# HydraNFC_v1_1_Rev1.net
KiCad netlist of a schematic drawn in EAGLE
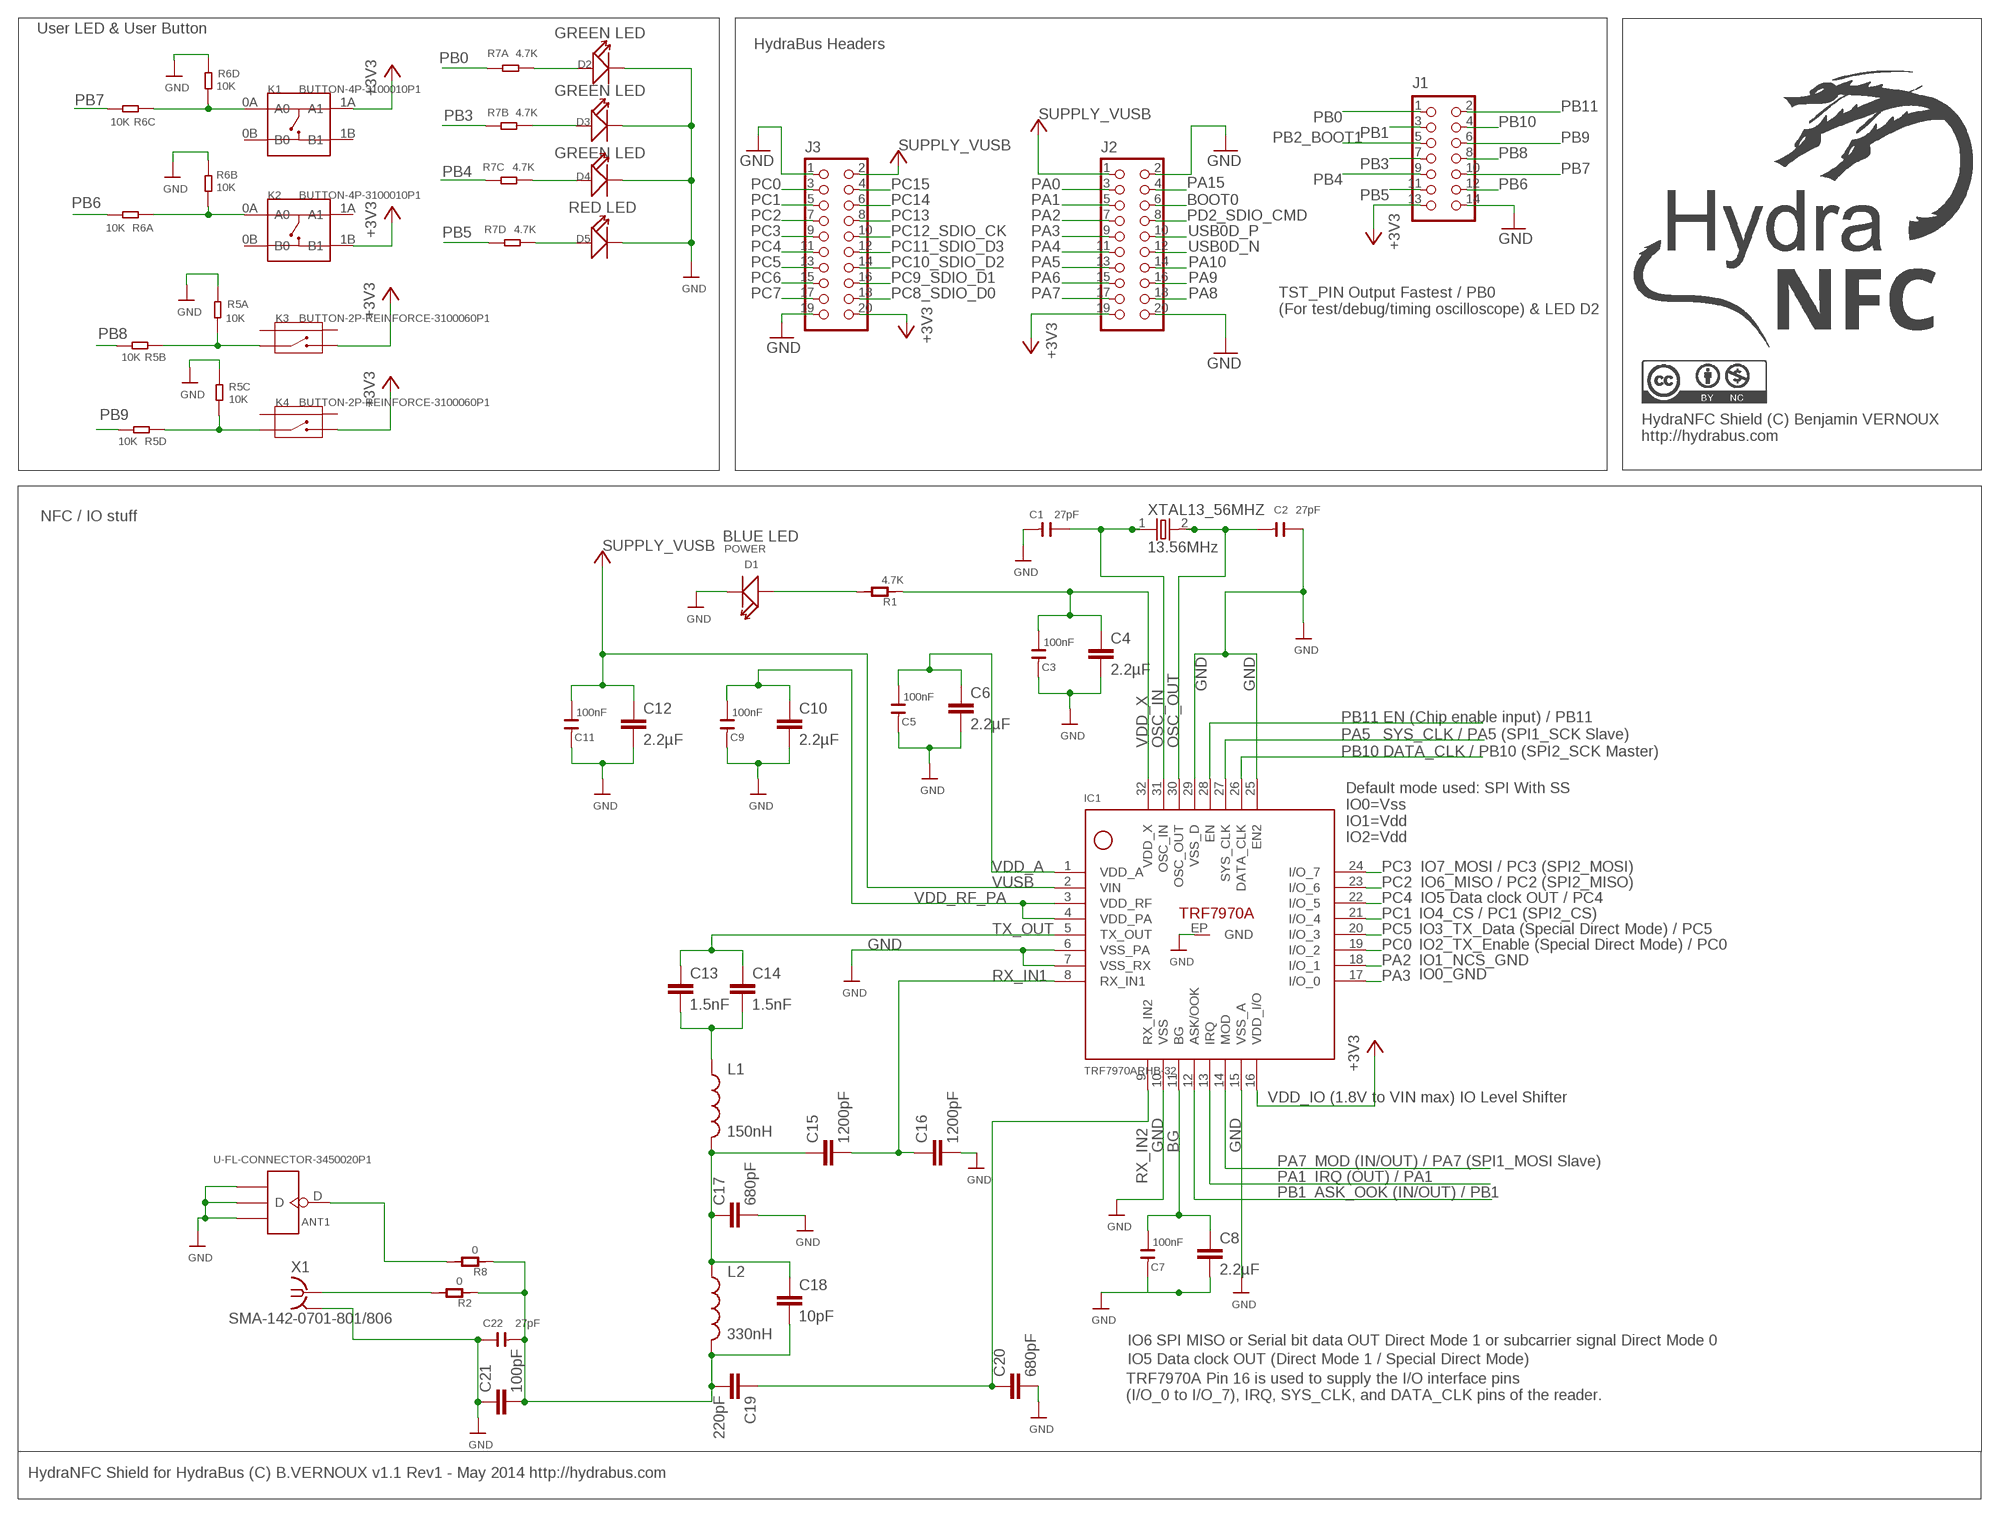
[diagram p0: schematic, sheet 1]

(export (version "E")
  (design (tool "Eeschema 10.0.6"))
  (components
    (comp (ref "ANT1")
      (value "U-FL-CONNECTOR-3450020P1")
      (footprint "eagle-import:U-FL")
      (libsource (lib "eagle-import") (part "U-FL-CONNECTOR-3450020P1"))
    )
    (comp (ref "C1")
      (value "27pF")
      (footprint "eagle-import:C0603")
      (libsource (lib "eagle-import") (part "C-0603"))
    )
    (comp (ref "C2")
      (value "27pF")
      (footprint "eagle-import:C0603")
      (libsource (lib "eagle-import") (part "C-0603"))
    )
    (comp (ref "C3")
      (value "100nF")
      (footprint "eagle-import:C0603")
      (libsource (lib "eagle-import") (part "C-0603"))
    )
    (comp (ref "C4")
      (value "2.2µF")
      (footprint "eagle-import:C805")
      (libsource (lib "eagle-import") (part "CAPC805"))
    )
    (comp (ref "C5")
      (value "100nF")
      (footprint "eagle-import:C0603")
      (libsource (lib "eagle-import") (part "C-0603"))
    )
    (comp (ref "C6")
      (value "2.2µF")
      (footprint "eagle-import:C805")
      (libsource (lib "eagle-import") (part "CAPC805"))
    )
    (comp (ref "C7")
      (value "100nF")
      (footprint "eagle-import:C0603")
      (libsource (lib "eagle-import") (part "C-0603"))
    )
    (comp (ref "C8")
      (value "2.2µF")
      (footprint "eagle-import:C805")
      (libsource (lib "eagle-import") (part "CAPC805"))
    )
    (comp (ref "C9")
      (value "100nF")
      (footprint "eagle-import:C0603")
      (libsource (lib "eagle-import") (part "C-0603"))
    )
    (comp (ref "C10")
      (value "2.2µF")
      (footprint "eagle-import:C805")
      (libsource (lib "eagle-import") (part "CAPC805"))
    )
    (comp (ref "C11")
      (value "100nF")
      (footprint "eagle-import:C0603")
      (libsource (lib "eagle-import") (part "C-0603"))
    )
    (comp (ref "C12")
      (value "2.2µF")
      (footprint "eagle-import:C805")
      (libsource (lib "eagle-import") (part "CAPC805"))
    )
    (comp (ref "C13")
      (value "1.5nF")
      (footprint "eagle-import:C805")
      (libsource (lib "eagle-import") (part "CAPC805"))
    )
    (comp (ref "C14")
      (value "1.5nF")
      (footprint "eagle-import:C805")
      (libsource (lib "eagle-import") (part "CAPC805"))
    )
    (comp (ref "C15")
      (value "1200pF")
      (footprint "eagle-import:C805")
      (libsource (lib "eagle-import") (part "CAPC805"))
    )
    (comp (ref "C16")
      (value "1200pF")
      (footprint "eagle-import:C805")
      (libsource (lib "eagle-import") (part "CAPC805"))
    )
    (comp (ref "C17")
      (value "680pF")
      (footprint "eagle-import:C805")
      (libsource (lib "eagle-import") (part "CAPC805"))
    )
    (comp (ref "C18")
      (value "10pF")
      (footprint "eagle-import:C805")
      (libsource (lib "eagle-import") (part "CAPC805"))
    )
    (comp (ref "C19")
      (value "220pF")
      (footprint "eagle-import:C805")
      (libsource (lib "eagle-import") (part "CAPC805"))
    )
    (comp (ref "C20")
      (value "680pF")
      (footprint "eagle-import:C805")
      (libsource (lib "eagle-import") (part "CAPC805"))
    )
    (comp (ref "C21")
      (value "100pF")
      (footprint "eagle-import:C805")
      (libsource (lib "eagle-import") (part "CAPC805"))
    )
    (comp (ref "C22")
      (value "27pF")
      (footprint "eagle-import:C0603")
      (libsource (lib "eagle-import") (part "C-0603"))
    )
    (comp (ref "D1")
      (value "POWER")
      (footprint "eagle-import:LED0603")
      (libsource (lib "eagle-import") (part "LED"))
    )
    (comp (ref "D2")
      (value "LED")
      (footprint "eagle-import:LED0603")
      (libsource (lib "eagle-import") (part "OPL Eagle Library_LED"))
    )
    (comp (ref "D3")
      (value "LED")
      (footprint "eagle-import:LED0603")
      (libsource (lib "eagle-import") (part "OPL Eagle Library_LED"))
    )
    (comp (ref "D4")
      (value "LED")
      (footprint "eagle-import:LED0603")
      (libsource (lib "eagle-import") (part "OPL Eagle Library_LED"))
    )
    (comp (ref "D5")
      (value "LED")
      (footprint "eagle-import:LED0603")
      (libsource (lib "eagle-import") (part "OPL Eagle Library_LED"))
    )
    (comp (ref "IC1")
      (value "TRF7970ARHB-32")
      (footprint "eagle-import:TRF7970A")
      (libsource (lib "eagle-import") (part "TRF7970A"))
    )
    (comp (ref "J1")
      (value "HYDRABUS_SHIELD_CON_HEADER_2X07")
      (footprint "eagle-import:HYDRABUS_SHIELD_M2X7")
      (libsource (lib "eagle-import") (part "HYDRABUS_SHIELD_CON_HEADER_2X07"))
    )
    (comp (ref "J2")
      (value "HYDRABUS_SHIELD_CON_HEADER_2X10")
      (footprint "eagle-import:HYDRABUS_SHIELD_M2X10")
      (libsource (lib "eagle-import") (part "HYDRABUS_SHIELD_CON_HEADER_2X10"))
    )
    (comp (ref "J3")
      (value "HYDRABUS_SHIELD_CON_HEADER_2X10")
      (footprint "eagle-import:HYDRABUS_SHIELD_M2X10")
      (libsource (lib "eagle-import") (part "HYDRABUS_SHIELD_CON_HEADER_2X10"))
    )
    (comp (ref "K1")
      (value "BUTTON-4P-3100010P1")
      (footprint "eagle-import:4P-SMD-6.0X6.0X5.0H")
      (libsource (lib "eagle-import") (part "BUTTON-4P-3100010P1"))
    )
    (comp (ref "K2")
      (value "BUTTON-4P-3100010P1")
      (footprint "eagle-import:4P-SMD-6.0X6.0X5.0H")
      (libsource (lib "eagle-import") (part "BUTTON-4P-3100010P1"))
    )
    (comp (ref "K3")
      (value "BUTTON-2P-REINFORCE-3100060P1")
      (footprint "eagle-import:4P-SMD-7.0X3.5X3.5H-90D")
      (libsource (lib "eagle-import") (part "BUTTON-2P-REINFORCE-3100060P1"))
    )
    (comp (ref "K4")
      (value "BUTTON-2P-REINFORCE-3100060P1")
      (footprint "eagle-import:4P-SMD-7.0X3.5X3.5H-90D")
      (libsource (lib "eagle-import") (part "BUTTON-2P-REINFORCE-3100060P1"))
    )
    (comp (ref "L1")
      (value "150nH")
      (footprint "eagle-import:1210")
      (libsource (lib "eagle-import") (part "INDUCTOR1210"))
    )
    (comp (ref "L2")
      (value "330nH")
      (footprint "eagle-import:1210")
      (libsource (lib "eagle-import") (part "INDUCTOR1210"))
    )
    (comp (ref "R1")
      (value "4.7K")
      (footprint "eagle-import:R0603")
      (libsource (lib "eagle-import") (part "R-0603"))
    )
    (comp (ref "R2")
      (value "0")
      (footprint "eagle-import:R0603")
      (libsource (lib "eagle-import") (part "R-0603"))
    )
    (comp (ref "R5")
      (value "10K")
      (footprint "eagle-import:R1206-8")
      (fields (field (name "OPL") "0040070P1"))
      (libsource (lib "eagle-import") (part "R-4R"))
    )
    (comp (ref "R6")
      (value "10K")
      (footprint "eagle-import:R1206-8")
      (fields (field (name "OPL") "0040070P1"))
      (libsource (lib "eagle-import") (part "R-4R"))
    )
    (comp (ref "R7")
      (value "4.7K")
      (footprint "eagle-import:R1206-8")
      (fields (field (name "OPL") "0040040P1"))
      (libsource (lib "eagle-import") (part "R-4R"))
    )
    (comp (ref "R8")
      (value "0")
      (footprint "eagle-import:R0603")
      (libsource (lib "eagle-import") (part "R-0603"))
    )
    (comp (ref "X1")
      (value "SMA-142-0701-801/806")
      (footprint "eagle-import:J502-ND-142-0701-801_806")
      (fields (field (name "MF") "JOHNSON COMPONENTS") (field (name "MPN") "142-0701-801"))
      (libsource (lib "eagle-import") (part "SMA-142-0701-801/806"))
    )
    (comp (ref "XTAL13_56MHZ")
      (value "13.56MHz")
      (footprint "eagle-import:HC-49U")
      (libsource (lib "eagle-import") (part "OSC-XTAL"))
    )
  )
  (nets
    (net (code "1") (name "+3V3") (class "Default")
      (node (ref "IC1") (pin "16") (pinfunction "VDD_I/O_16") (pintype "input"))
      (node (ref "J1") (pin "13") (pinfunction "13_13") (pintype "passive"))
      (node (ref "J2") (pin "19") (pinfunction "19_19") (pintype "passive"))
      (node (ref "J3") (pin "20") (pinfunction "20_20") (pintype "passive"))
      (node (ref "K1") (pin "1A") (pinfunction "A1_1A") (pintype "bidirectional"))
      (node (ref "K2") (pin "1B") (pinfunction "B1_1B") (pintype "bidirectional"))
      (node (ref "K3") (pin "2") (pinfunction "2_2") (pintype "bidirectional"))
      (node (ref "K4") (pin "2") (pinfunction "2_2") (pintype "bidirectional"))
    )
    (net (code "2") (name "/BG") (class "Default")
      (node (ref "C7") (pin "2") (pinfunction "2_2") (pintype "bidirectional"))
      (node (ref "C8") (pin "1") (pinfunction "1_1") (pintype "passive"))
      (node (ref "IC1") (pin "11") (pinfunction "BG_11") (pintype "output"))
    )
    (net (code "3") (name "/BOOT0") (class "Default")
      (node (ref "J2") (pin "6") (pinfunction "6_6") (pintype "passive"))
    )
    (net (code "4") (name "/OSC_IN") (class "Default")
      (node (ref "C1") (pin "2") (pinfunction "2_2") (pintype "bidirectional"))
      (node (ref "IC1") (pin "31") (pinfunction "OSC_IN_31") (pintype "bidirectional"))
      (node (ref "XTAL13_56MHZ") (pin "1") (pinfunction "1_1") (pintype "passive"))
    )
    (net (code "5") (name "/OSC_OUT") (class "Default")
      (node (ref "C2") (pin "1") (pinfunction "1_1") (pintype "bidirectional"))
      (node (ref "IC1") (pin "30") (pinfunction "OSC_OUT_30") (pintype "output"))
      (node (ref "XTAL13_56MHZ") (pin "2") (pinfunction "2_2") (pintype "passive"))
    )
    (net (code "6") (name "/PA0") (class "Default")
      (node (ref "J2") (pin "3") (pinfunction "3_3") (pintype "passive"))
    )
    (net (code "7") (name "/PA1") (class "Default")
      (node (ref "IC1") (pin "13") (pinfunction "IRQ_13") (pintype "output"))
      (node (ref "J2") (pin "5") (pinfunction "5_5") (pintype "passive"))
    )
    (net (code "8") (name "/PA2") (class "Default")
      (node (ref "IC1") (pin "18") (pinfunction "I/O_1_18") (pintype "bidirectional"))
      (node (ref "J2") (pin "7") (pinfunction "7_7") (pintype "passive"))
    )
    (net (code "9") (name "/PA3") (class "Default")
      (node (ref "IC1") (pin "17") (pinfunction "I/O_0_17") (pintype "bidirectional"))
      (node (ref "J2") (pin "9") (pinfunction "9_9") (pintype "passive"))
    )
    (net (code "10") (name "/PA4") (class "Default")
      (node (ref "J2") (pin "11") (pinfunction "11_11") (pintype "passive"))
    )
    (net (code "11") (name "/PA5") (class "Default")
      (node (ref "IC1") (pin "27") (pinfunction "SYS_CLK_27") (pintype "output"))
      (node (ref "J2") (pin "13") (pinfunction "13_13") (pintype "passive"))
    )
    (net (code "12") (name "/PA6") (class "Default")
      (node (ref "J2") (pin "15") (pinfunction "15_15") (pintype "passive"))
    )
    (net (code "13") (name "/PA7") (class "Default")
      (node (ref "IC1") (pin "14") (pinfunction "MOD_14") (pintype "bidirectional"))
      (node (ref "J2") (pin "17") (pinfunction "17_17") (pintype "passive"))
    )
    (net (code "14") (name "/PA8") (class "Default")
      (node (ref "J2") (pin "18") (pinfunction "18_18") (pintype "passive"))
    )
    (net (code "15") (name "/PA9") (class "Default")
      (node (ref "J2") (pin "16") (pinfunction "16_16") (pintype "passive"))
    )
    (net (code "16") (name "/PA10") (class "Default")
      (node (ref "J2") (pin "14") (pinfunction "14_14") (pintype "passive"))
    )
    (net (code "17") (name "/PA15") (class "Default")
      (node (ref "J2") (pin "4") (pinfunction "4_4") (pintype "passive"))
    )
    (net (code "18") (name "/PB0") (class "Default")
      (node (ref "J1") (pin "1") (pinfunction "1_1") (pintype "passive"))
      (node (ref "R7") (pin "1") (pinfunction "1_1") (pintype "passive"))
    )
    (net (code "19") (name "/PB1") (class "Default")
      (node (ref "IC1") (pin "12") (pinfunction "ASK/OOK_12") (pintype "bidirectional"))
      (node (ref "J1") (pin "3") (pinfunction "3_3") (pintype "passive"))
    )
    (net (code "20") (name "/PB2_BOOT1") (class "Default")
      (node (ref "J1") (pin "5") (pinfunction "5_5") (pintype "passive"))
    )
    (net (code "21") (name "/PB3") (class "Default")
      (node (ref "J1") (pin "7") (pinfunction "7_7") (pintype "passive"))
      (node (ref "R7") (pin "2") (pinfunction "1_2") (pintype "passive"))
    )
    (net (code "22") (name "/PB4") (class "Default")
      (node (ref "J1") (pin "9") (pinfunction "9_9") (pintype "passive"))
      (node (ref "R7") (pin "3") (pinfunction "1_3") (pintype "passive"))
    )
    (net (code "23") (name "/PB5") (class "Default")
      (node (ref "J1") (pin "11") (pinfunction "11_11") (pintype "passive"))
      (node (ref "R7") (pin "4") (pinfunction "1_4") (pintype "passive"))
    )
    (net (code "24") (name "/PB6") (class "Default")
      (node (ref "J1") (pin "12") (pinfunction "12_12") (pintype "passive"))
      (node (ref "R6") (pin "1") (pinfunction "1_1") (pintype "passive"))
    )
    (net (code "25") (name "/PB7") (class "Default")
      (node (ref "J1") (pin "10") (pinfunction "10_10") (pintype "passive"))
      (node (ref "R6") (pin "6") (pinfunction "2_6") (pintype "passive"))
    )
    (net (code "26") (name "/PB8") (class "Default")
      (node (ref "J1") (pin "8") (pinfunction "8_8") (pintype "passive"))
      (node (ref "R5") (pin "7") (pinfunction "2_7") (pintype "passive"))
    )
    (net (code "27") (name "/PB9") (class "Default")
      (node (ref "J1") (pin "6") (pinfunction "6_6") (pintype "passive"))
      (node (ref "R5") (pin "4") (pinfunction "1_4") (pintype "passive"))
    )
    (net (code "28") (name "/PB10") (class "Default")
      (node (ref "IC1") (pin "26") (pinfunction "DATA_CLK_26") (pintype "input"))
      (node (ref "J1") (pin "4") (pinfunction "4_4") (pintype "passive"))
    )
    (net (code "29") (name "/PB11") (class "Default")
      (node (ref "IC1") (pin "28") (pinfunction "EN_28") (pintype "input"))
      (node (ref "J1") (pin "2") (pinfunction "2_2") (pintype "passive"))
    )
    (net (code "30") (name "/PC0") (class "Default")
      (node (ref "IC1") (pin "19") (pinfunction "I/O_2_19") (pintype "bidirectional"))
      (node (ref "J3") (pin "3") (pinfunction "3_3") (pintype "passive"))
    )
    (net (code "31") (name "/PC1") (class "Default")
      (node (ref "IC1") (pin "21") (pinfunction "I/O_4_21") (pintype "bidirectional"))
      (node (ref "J3") (pin "5") (pinfunction "5_5") (pintype "passive"))
    )
    (net (code "32") (name "/PC2") (class "Default")
      (node (ref "IC1") (pin "23") (pinfunction "I/O_6_23") (pintype "bidirectional"))
      (node (ref "J3") (pin "7") (pinfunction "7_7") (pintype "passive"))
    )
    (net (code "33") (name "/PC3") (class "Default")
      (node (ref "IC1") (pin "24") (pinfunction "I/O_7_24") (pintype "bidirectional"))
      (node (ref "J3") (pin "9") (pinfunction "9_9") (pintype "passive"))
    )
    (net (code "34") (name "/PC4") (class "Default")
      (node (ref "IC1") (pin "22") (pinfunction "I/O_5_22") (pintype "bidirectional"))
      (node (ref "J3") (pin "11") (pinfunction "11_11") (pintype "passive"))
    )
    (net (code "35") (name "/PC5") (class "Default")
      (node (ref "IC1") (pin "20") (pinfunction "I/O_3_20") (pintype "bidirectional"))
      (node (ref "J3") (pin "13") (pinfunction "13_13") (pintype "passive"))
    )
    (net (code "36") (name "/PC6") (class "Default")
      (node (ref "J3") (pin "15") (pinfunction "15_15") (pintype "passive"))
    )
    (net (code "37") (name "/PC7") (class "Default")
      (node (ref "J3") (pin "17") (pinfunction "17_17") (pintype "passive"))
    )
    (net (code "38") (name "/PC8_SDIO_D0") (class "Default")
      (node (ref "J3") (pin "18") (pinfunction "18_18") (pintype "passive"))
    )
    (net (code "39") (name "/PC9_SDIO_D1") (class "Default")
      (node (ref "J3") (pin "16") (pinfunction "16_16") (pintype "passive"))
    )
    (net (code "40") (name "/PC10_SDIO_D2") (class "Default")
      (node (ref "J3") (pin "14") (pinfunction "14_14") (pintype "passive"))
    )
    (net (code "41") (name "/PC11_SDIO_D3") (class "Default")
      (node (ref "J3") (pin "12") (pinfunction "12_12") (pintype "passive"))
    )
    (net (code "42") (name "/PC12_SDIO_CK") (class "Default")
      (node (ref "J3") (pin "10") (pinfunction "10_10") (pintype "passive"))
    )
    (net (code "43") (name "/PC13") (class "Default")
      (node (ref "J3") (pin "8") (pinfunction "8_8") (pintype "passive"))
    )
    (net (code "44") (name "/PC14") (class "Default")
      (node (ref "J3") (pin "6") (pinfunction "6_6") (pintype "passive"))
    )
    (net (code "45") (name "/PC15") (class "Default")
      (node (ref "J3") (pin "4") (pinfunction "4_4") (pintype "passive"))
    )
    (net (code "46") (name "/PD2_SDIO_CMD") (class "Default")
      (node (ref "J2") (pin "8") (pinfunction "8_8") (pintype "passive"))
    )
    (net (code "47") (name "/RX_IN1") (class "Default")
      (node (ref "C15") (pin "2") (pinfunction "2_2") (pintype "passive"))
      (node (ref "C16") (pin "1") (pinfunction "1_1") (pintype "passive"))
      (node (ref "IC1") (pin "8") (pinfunction "RX_IN1_8") (pintype "input"))
    )
    (net (code "48") (name "/RX_IN2") (class "Default")
      (node (ref "C19") (pin "1") (pinfunction "1_1") (pintype "passive"))
      (node (ref "C20") (pin "1") (pinfunction "1_1") (pintype "passive"))
      (node (ref "IC1") (pin "9") (pinfunction "RX_IN2_9") (pintype "input"))
    )
    (net (code "49") (name "/TX_OUT") (class "Default")
      (node (ref "C13") (pin "1") (pinfunction "1_1") (pintype "passive"))
      (node (ref "C14") (pin "1") (pinfunction "1_1") (pintype "passive"))
      (node (ref "IC1") (pin "5") (pinfunction "TX_OUT_5") (pintype "output"))
    )
    (net (code "50") (name "/USB0D_N") (class "Default")
      (node (ref "J2") (pin "12") (pinfunction "12_12") (pintype "passive"))
    )
    (net (code "51") (name "/USB0D_P") (class "Default")
      (node (ref "J2") (pin "10") (pinfunction "10_10") (pintype "passive"))
    )
    (net (code "52") (name "/VDD_A") (class "Default")
      (node (ref "C5") (pin "2") (pinfunction "2_2") (pintype "bidirectional"))
      (node (ref "C6") (pin "1") (pinfunction "1_1") (pintype "passive"))
      (node (ref "IC1") (pin "1") (pinfunction "VDD_A_1") (pintype "output"))
    )
    (net (code "53") (name "/VDD_RF_PA") (class "Default")
      (node (ref "C10") (pin "1") (pinfunction "1_1") (pintype "passive"))
      (node (ref "C9") (pin "2") (pinfunction "2_2") (pintype "bidirectional"))
      (node (ref "IC1") (pin "3") (pinfunction "VDD_RF_3") (pintype "output"))
      (node (ref "IC1") (pin "4") (pinfunction "VDD_PA_4") (pintype "input"))
    )
    (net (code "54") (name "/VDD_X") (class "Default")
      (node (ref "C3") (pin "2") (pinfunction "2_2") (pintype "bidirectional"))
      (node (ref "C4") (pin "1") (pinfunction "1_1") (pintype "passive"))
      (node (ref "IC1") (pin "32") (pinfunction "VDD_X_32") (pintype "output"))
      (node (ref "R1") (pin "2") (pinfunction "2_2") (pintype "bidirectional"))
    )
    (net (code "55") (name "GND") (class "Default")
      (node (ref "ANT1") (pin "GND1") (pinfunction "GND1_GND1") (pintype "bidirectional"))
      (node (ref "ANT1") (pin "GND2") (pinfunction "GND2_GND2") (pintype "bidirectional"))
      (node (ref "ANT1") (pin "GND3") (pinfunction "GND3_GND3") (pintype "bidirectional"))
      (node (ref "C1") (pin "1") (pinfunction "1_1") (pintype "bidirectional"))
      (node (ref "C10") (pin "2") (pinfunction "2_2") (pintype "passive"))
      (node (ref "C11") (pin "1") (pinfunction "1_1") (pintype "bidirectional"))
      (node (ref "C12") (pin "2") (pinfunction "2_2") (pintype "passive"))
      (node (ref "C16") (pin "2") (pinfunction "2_2") (pintype "passive"))
      (node (ref "C17") (pin "2") (pinfunction "2_2") (pintype "passive"))
      (node (ref "C2") (pin "2") (pinfunction "2_2") (pintype "bidirectional"))
      (node (ref "C20") (pin "2") (pinfunction "2_2") (pintype "passive"))
      (node (ref "C21") (pin "1") (pinfunction "1_1") (pintype "passive"))
      (node (ref "C22") (pin "2") (pinfunction "2_2") (pintype "bidirectional"))
      (node (ref "C3") (pin "1") (pinfunction "1_1") (pintype "bidirectional"))
      (node (ref "C4") (pin "2") (pinfunction "2_2") (pintype "passive"))
      (node (ref "C5") (pin "1") (pinfunction "1_1") (pintype "bidirectional"))
      (node (ref "C6") (pin "2") (pinfunction "2_2") (pintype "passive"))
      (node (ref "C7") (pin "1") (pinfunction "1_1") (pintype "bidirectional"))
      (node (ref "C8") (pin "2") (pinfunction "2_2") (pintype "passive"))
      (node (ref "C9") (pin "1") (pinfunction "1_1") (pintype "bidirectional"))
      (node (ref "D1") (pin "-") (pinfunction "-_-") (pintype "passive"))
      (node (ref "D2") (pin "-") (pinfunction "-_-") (pintype "passive"))
      (node (ref "D3") (pin "-") (pinfunction "-_-") (pintype "passive"))
      (node (ref "D4") (pin "-") (pinfunction "-_-") (pintype "passive"))
      (node (ref "D5") (pin "-") (pinfunction "-_-") (pintype "passive"))
      (node (ref "IC1") (pin "10") (pinfunction "VSS_10") (pintype "power_in"))
      (node (ref "IC1") (pin "15") (pinfunction "VSS_A_15") (pintype "power_in"))
      (node (ref "IC1") (pin "25") (pinfunction "EN2_25") (pintype "input"))
      (node (ref "IC1") (pin "29") (pinfunction "VSS_D_29") (pintype "power_in"))
      (node (ref "IC1") (pin "6") (pinfunction "VSS_PA_6") (pintype "power_in"))
      (node (ref "IC1") (pin "7") (pinfunction "VSS_RX_7") (pintype "power_in"))
      (node (ref "IC1") (pin "EP") (pinfunction "GND_EP") (pintype "bidirectional"))
      (node (ref "J1") (pin "14") (pinfunction "14_14") (pintype "passive"))
      (node (ref "J2") (pin "2") (pinfunction "2_2") (pintype "passive"))
      (node (ref "J2") (pin "20") (pinfunction "20_20") (pintype "passive"))
      (node (ref "J3") (pin "1") (pinfunction "1_1") (pintype "passive"))
      (node (ref "J3") (pin "19") (pinfunction "19_19") (pintype "passive"))
      (node (ref "R5") (pin "3") (pinfunction "1_3") (pintype "passive"))
      (node (ref "R5") (pin "8") (pinfunction "2_8") (pintype "passive"))
      (node (ref "R6") (pin "4") (pinfunction "1_4") (pintype "passive"))
      (node (ref "R6") (pin "7") (pinfunction "2_7") (pintype "passive"))
      (node (ref "X1") (pin "G@1") (pinfunction "GND_G@1") (pintype "power_in"))
    )
    (net (code "56") (name "Net-(ANT1-PadD)") (class "Default")
      (node (ref "ANT1") (pin "D") (pinfunction "D_D") (pintype "bidirectional"))
      (node (ref "R8") (pin "1") (pinfunction "1_1") (pintype "bidirectional"))
    )
    (net (code "57") (name "Net-(C13-Pad2)") (class "Default")
      (node (ref "C13") (pin "2") (pinfunction "2_2") (pintype "passive"))
      (node (ref "C14") (pin "2") (pinfunction "2_2") (pintype "passive"))
      (node (ref "L1") (pin "1") (pinfunction "1_1") (pintype "passive"))
    )
    (net (code "58") (name "Net-(C15-Pad1)") (class "Default")
      (node (ref "C15") (pin "1") (pinfunction "1_1") (pintype "passive"))
      (node (ref "C17") (pin "1") (pinfunction "1_1") (pintype "passive"))
      (node (ref "C18") (pin "1") (pinfunction "1_1") (pintype "passive"))
      (node (ref "L1") (pin "2") (pinfunction "2_2") (pintype "passive"))
      (node (ref "L2") (pin "1") (pinfunction "1_1") (pintype "passive"))
    )
    (net (code "59") (name "Net-(C18-Pad2)") (class "Default")
      (node (ref "C18") (pin "2") (pinfunction "2_2") (pintype "passive"))
      (node (ref "C19") (pin "2") (pinfunction "2_2") (pintype "passive"))
      (node (ref "C21") (pin "2") (pinfunction "2_2") (pintype "passive"))
      (node (ref "C22") (pin "1") (pinfunction "1_1") (pintype "bidirectional"))
      (node (ref "L2") (pin "2") (pinfunction "2_2") (pintype "passive"))
      (node (ref "R2") (pin "2") (pinfunction "2_2") (pintype "bidirectional"))
      (node (ref "R8") (pin "2") (pinfunction "2_2") (pintype "bidirectional"))
    )
    (net (code "60") (name "Net-(D1-Pad+)") (class "Default")
      (node (ref "D1") (pin "+") (pinfunction "+_+") (pintype "passive"))
      (node (ref "R1") (pin "1") (pinfunction "1_1") (pintype "bidirectional"))
    )
    (net (code "61") (name "Net-(K1-A0)") (class "Default")
      (node (ref "K1") (pin "0A") (pinfunction "A0_0A") (pintype "bidirectional"))
      (node (ref "R6") (pin "3") (pinfunction "1_3") (pintype "passive"))
      (node (ref "R6") (pin "5") (pinfunction "2_5") (pintype "passive"))
    )
    (net (code "62") (name "Net-(K2-A0)") (class "Default")
      (node (ref "K2") (pin "0A") (pinfunction "A0_0A") (pintype "bidirectional"))
      (node (ref "R6") (pin "2") (pinfunction "1_2") (pintype "passive"))
      (node (ref "R6") (pin "8") (pinfunction "2_8") (pintype "passive"))
    )
    (net (code "63") (name "Net-(R2-Pad1)") (class "Default")
      (node (ref "R2") (pin "1") (pinfunction "1_1") (pintype "bidirectional"))
      (node (ref "X1") (pin "1") (pinfunction "1_1") (pintype "passive"))
    )
    (net (code "64") (name "Net-(R5B-1)") (class "Default")
      (node (ref "K3") (pin "1") (pinfunction "1_1") (pintype "bidirectional"))
      (node (ref "R5") (pin "1") (pinfunction "1_1") (pintype "passive"))
      (node (ref "R5") (pin "2") (pinfunction "1_2") (pintype "passive"))
    )
    (net (code "65") (name "Net-(R5C-2)") (class "Default")
      (node (ref "K4") (pin "1") (pinfunction "1_1") (pintype "bidirectional"))
      (node (ref "R5") (pin "5") (pinfunction "2_5") (pintype "passive"))
      (node (ref "R5") (pin "6") (pinfunction "2_6") (pintype "passive"))
    )
    (net (code "66") (name "Net-(R7A-2)") (class "Default")
      (node (ref "D2") (pin "+") (pinfunction "+_+") (pintype "passive"))
      (node (ref "R7") (pin "8") (pinfunction "2_8") (pintype "passive"))
    )
    (net (code "67") (name "Net-(R7B-2)") (class "Default")
      (node (ref "D3") (pin "+") (pinfunction "+_+") (pintype "passive"))
      (node (ref "R7") (pin "7") (pinfunction "2_7") (pintype "passive"))
    )
    (net (code "68") (name "Net-(R7C-2)") (class "Default")
      (node (ref "D4") (pin "+") (pinfunction "+_+") (pintype "passive"))
      (node (ref "R7") (pin "6") (pinfunction "2_6") (pintype "passive"))
    )
    (net (code "69") (name "Net-(R7D-2)") (class "Default")
      (node (ref "D5") (pin "+") (pinfunction "+_+") (pintype "passive"))
      (node (ref "R7") (pin "5") (pinfunction "2_5") (pintype "passive"))
    )
    (net (code "70") (name "SUPPLY_VUSB") (class "Default")
      (node (ref "C11") (pin "2") (pinfunction "2_2") (pintype "bidirectional"))
      (node (ref "C12") (pin "1") (pinfunction "1_1") (pintype "passive"))
      (node (ref "IC1") (pin "2") (pinfunction "VIN_2") (pintype "power_in"))
      (node (ref "J2") (pin "1") (pinfunction "1_1") (pintype "passive"))
      (node (ref "J3") (pin "2") (pinfunction "2_2") (pintype "passive"))
    )
    (net (code "71") (name "unconnected-(K1-B0-Pad0B)") (class "Default")
      (node (ref "K1") (pin "0B") (pinfunction "B0_0B") (pintype "bidirectional"))
    )
    (net (code "72") (name "unconnected-(K1-B1-Pad1B)") (class "Default")
      (node (ref "K1") (pin "1B") (pinfunction "B1_1B") (pintype "bidirectional"))
    )
    (net (code "73") (name "unconnected-(K2-A1-Pad1A)") (class "Default")
      (node (ref "K2") (pin "1A") (pinfunction "A1_1A") (pintype "bidirectional"))
    )
    (net (code "74") (name "unconnected-(K2-B0-Pad0B)") (class "Default")
      (node (ref "K2") (pin "0B") (pinfunction "B0_0B") (pintype "bidirectional"))
    )
    (net (code "75") (name "unconnected-(K3-PadS1)") (class "Default")
      (node (ref "K3") (pin "S1") (pinfunction "S1_S1") (pintype "bidirectional"))
    )
    (net (code "76") (name "unconnected-(K3-PadS2)") (class "Default")
      (node (ref "K3") (pin "S2") (pinfunction "S2_S2") (pintype "bidirectional"))
    )
    (net (code "77") (name "unconnected-(K4-PadS1)") (class "Default")
      (node (ref "K4") (pin "S1") (pinfunction "S1_S1") (pintype "bidirectional"))
    )
    (net (code "78") (name "unconnected-(K4-PadS2)") (class "Default")
      (node (ref "K4") (pin "S2") (pinfunction "S2_S2") (pintype "bidirectional"))
    )
  )
)
